# Carte_Affichage.net
KiCad netlist of a schematic drawn in EAGLE
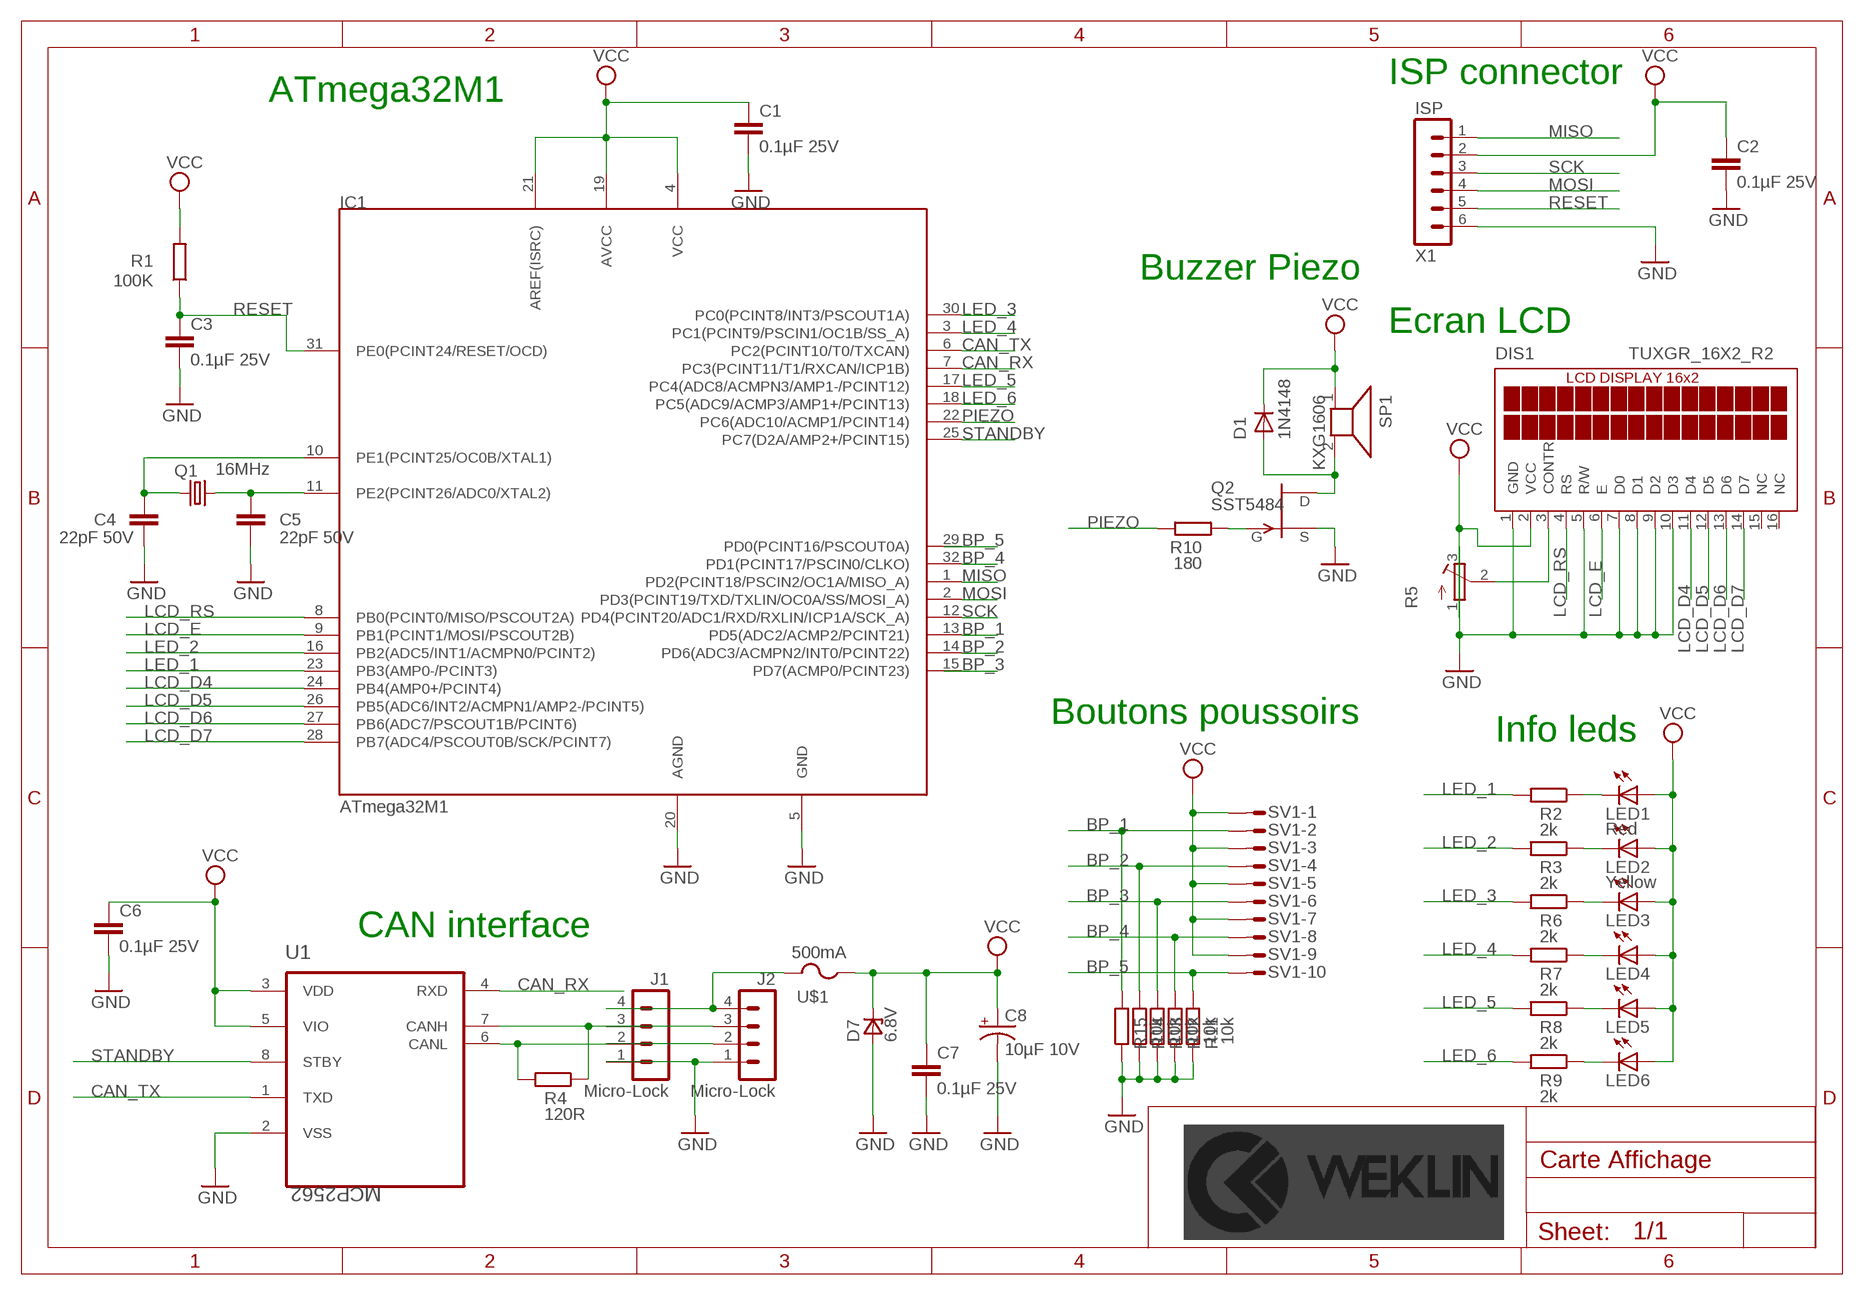
[diagram p0: schematic, sheet 1]

(export (version "E")
  (design (tool "Eeschema 10.0.6"))
  (components
    (comp (ref "C1")
      (value "0.1µF 25V")
      (footprint "eagle-import:C2012")
      (fields (field (name "MANUFACTURER") "AVX") (field (name "MPN") "08053C104KAT2A"))
      (libsource (lib "eagle-import") (part "CAPACITOR_NON_POL-0.1µF-25V(+-10%)(2012)"))
    )
    (comp (ref "C2")
      (value "0.1µF 25V")
      (footprint "eagle-import:C2012")
      (fields (field (name "MANUFACTURER") "AVX") (field (name "MPN") "08053C104KAT2A"))
      (libsource (lib "eagle-import") (part "CAPACITOR_NON_POL-0.1µF-25V(+-10%)(2012)"))
    )
    (comp (ref "C3")
      (value "0.1µF 25V")
      (footprint "eagle-import:C2012")
      (fields (field (name "MANUFACTURER") "AVX") (field (name "MPN") "08053C104KAT2A"))
      (libsource (lib "eagle-import") (part "CAPACITOR_NON_POL-0.1µF-25V(+-10%)(2012)"))
    )
    (comp (ref "C4")
      (value "22pF 50V")
      (footprint "eagle-import:C2012")
      (fields (field (name "MANUFACTURER") "Multicomp") (field (name "MPN") "MC0805N220J500CT"))
      (libsource (lib "eagle-import") (part "CAPACITOR_NON_POL-22PF-50V(+-5%)(2012)"))
    )
    (comp (ref "C5")
      (value "22pF 50V")
      (footprint "eagle-import:C2012")
      (fields (field (name "MANUFACTURER") "Multicomp") (field (name "MPN") "MC0805N220J500CT"))
      (libsource (lib "eagle-import") (part "CAPACITOR_NON_POL-22PF-50V(+-5%)(2012)"))
    )
    (comp (ref "C6")
      (value "0.1µF 25V")
      (footprint "eagle-import:C2012")
      (fields (field (name "MANUFACTURER") "AVX") (field (name "MPN") "08053C104KAT2A"))
      (libsource (lib "eagle-import") (part "CAPACITOR_NON_POL-0.1µF-25V(+-10%)(2012)"))
    )
    (comp (ref "C7")
      (value "0.1µF 25V")
      (footprint "eagle-import:C2012")
      (fields (field (name "MANUFACTURER") "AVX") (field (name "MPN") "08053C104KAT2A"))
      (libsource (lib "eagle-import") (part "CAPACITOR_NON_POL-0.1µF-25V(+-10%)(2012)"))
    )
    (comp (ref "C8")
      (value "10µF 10V")
      (footprint "eagle-import:EIA3216")
      (fields (field (name "MANUFACTURER") "Kemet") (field (name "MPN") "T491A106K010AT"))
      (libsource (lib "eagle-import") (part "CAPACITOR_POL-10µF-10V(+-10%)(3216)"))
    )
    (comp (ref "D1")
      (value "1N4148")
      (footprint "eagle-import:SMA-DO214AC")
      (libsource (lib "eagle-import") (part "GF1"))
    )
    (comp (ref "D7")
      (value "6.8V")
      (footprint "eagle-import:DO-214AA")
      (fields (field (name "MANUFACTURER") "ON Semiconductor") (field (name "MPN") "P6SMB6.8AT3G"))
      (libsource (lib "eagle-import") (part "ZENER_UNIDIR6.8"))
    )
    (comp (ref "DIS1")
      (value "TUXGR_16X2_R2")
      (footprint "eagle-import:TUXGR_16X2_R2")
      (libsource (lib "eagle-import") (part "TUXGR_16X2_R2"))
    )
    (comp (ref "IC1")
      (value "ATmega32M1")
      (footprint "eagle-import:TQFP32")
      (fields (field (name "MANUFACTURER") "Atmel") (field (name "MPN") "ATmega32M1-AU"))
      (libsource (lib "eagle-import") (part "ATMEGA32M1-TQFP32"))
    )
    (comp (ref "J1")
      (value "Micro-Lock")
      (footprint "eagle-import:504195-0470")
      (fields (field (name "MANUFACTURER") "Molex") (field (name "MPN") "504195-0470"))
      (libsource (lib "eagle-import") (part "MICROLOCK-4CMS"))
    )
    (comp (ref "J2")
      (value "Micro-Lock")
      (footprint "eagle-import:504195-0470")
      (fields (field (name "MANUFACTURER") "Molex") (field (name "MPN") "504195-0470"))
      (libsource (lib "eagle-import") (part "MICROLOCK-4CMS"))
    )
    (comp (ref "LED1")
      (value "Red")
      (footprint "eagle-import:VLD")
      (fields (field (name "MANUFACTURER") "Vishay") (field (name "MPN") "VLDS1235G"))
      (libsource (lib "eagle-import") (part "LEDVLDS1235G"))
    )
    (comp (ref "LED2")
      (value "Yellow")
      (footprint "eagle-import:VLD")
      (fields (field (name "MANUFACTURER") "Vishay") (field (name "MPN") "VLDY1235G"))
      (libsource (lib "eagle-import") (part "LED-VLDY1235G"))
    )
    (comp (ref "LED3")
      (value "LED5MM")
      (footprint "eagle-import:LED5MM")
      (libsource (lib "eagle-import") (part "LED5MM"))
    )
    (comp (ref "LED4")
      (value "LED5MM")
      (footprint "eagle-import:LED5MM")
      (libsource (lib "eagle-import") (part "LED5MM"))
    )
    (comp (ref "LED5")
      (value "LED5MM")
      (footprint "eagle-import:LED5MM")
      (libsource (lib "eagle-import") (part "LED5MM"))
    )
    (comp (ref "LED6")
      (value "LED5MM")
      (footprint "eagle-import:LED5MM")
      (libsource (lib "eagle-import") (part "LED5MM"))
    )
    (comp (ref "Q1")
      (value "16MHz")
      (footprint "eagle-import:SMD_KX7")
      (fields (field (name "MANUFACTURER") "AEL CRYSTALS") (field (name "MPN") "E3SB16.0000F09G11AE"))
      (libsource (lib "eagle-import") (part "CRYSTAL-16MHZ_SMD(3225)"))
    )
    (comp (ref "Q2")
      (value "SST5484")
      (footprint "eagle-import:SOT23")
      (libsource (lib "eagle-import") (part "?548SST4"))
    )
    (comp (ref "R1")
      (value "100K")
      (footprint "eagle-import:R2012")
      (fields (field (name "MANUFACTURER") "Multicomp") (field (name "MPN") "MCWR08X1003FTL"))
      (libsource (lib "eagle-import") (part "RESISTOR-100K(+-1%)(2012)"))
    )
    (comp (ref "R2")
      (value "2k")
      (footprint "eagle-import:R2012")
      (fields (field (name "MANUFACTURER") "Multicomp") (field (name "MPN") "MC0805S8F1101T5E"))
      (libsource (lib "eagle-import") (part "RESISTOR-1K1(+-1%)(2012)"))
    )
    (comp (ref "R3")
      (value "2k")
      (footprint "eagle-import:R2012")
      (fields (field (name "MANUFACTURER") "Multicomp") (field (name "MPN") "MC0805S8F1101T5E"))
      (libsource (lib "eagle-import") (part "RESISTOR-1K1(+-1%)(2012)"))
    )
    (comp (ref "R4")
      (value "120R")
      (footprint "eagle-import:R2012")
      (fields (field (name "MANUFACTURER") "Multicomp") (field (name "MPN") "MCWR08X1200FTL"))
      (libsource (lib "eagle-import") (part "RESISTOR-120R(+-1%)(2012)"))
    )
    (comp (ref "R5")
      (value "R-TRIMM3299W")
      (footprint "eagle-import:RTRIM3299W")
      (libsource (lib "eagle-import") (part "R-TRIMM3299W"))
    )
    (comp (ref "R6")
      (value "2k")
      (footprint "eagle-import:R2012")
      (fields (field (name "MANUFACTURER") "Multicomp") (field (name "MPN") "MC0805S8F1101T5E"))
      (libsource (lib "eagle-import") (part "RESISTOR-1K1(+-1%)(2012)"))
    )
    (comp (ref "R7")
      (value "2k")
      (footprint "eagle-import:R2012")
      (fields (field (name "MANUFACTURER") "Multicomp") (field (name "MPN") "MC0805S8F1101T5E"))
      (libsource (lib "eagle-import") (part "RESISTOR-1K1(+-1%)(2012)"))
    )
    (comp (ref "R8")
      (value "2k")
      (footprint "eagle-import:R2012")
      (fields (field (name "MANUFACTURER") "Multicomp") (field (name "MPN") "MC0805S8F1101T5E"))
      (libsource (lib "eagle-import") (part "RESISTOR-1K1(+-1%)(2012)"))
    )
    (comp (ref "R9")
      (value "2k")
      (footprint "eagle-import:R2012")
      (fields (field (name "MANUFACTURER") "Multicomp") (field (name "MPN") "MC0805S8F1101T5E"))
      (libsource (lib "eagle-import") (part "RESISTOR-1K1(+-1%)(2012)"))
    )
    (comp (ref "R10")
      (value "180")
      (footprint "eagle-import:R2012")
      (fields (field (name "MANUFACTURER") "Multicomp") (field (name "MPN") "MC0805S8F1101T5E"))
      (libsource (lib "eagle-import") (part "RESISTOR-1K1(+-1%)(2012)"))
    )
    (comp (ref "R11")
      (value "10k")
      (footprint "eagle-import:R2012")
      (fields (field (name "MANUFACTURER") "Multicomp") (field (name "MPN") "MC0805S8F1101T5E"))
      (libsource (lib "eagle-import") (part "RESISTOR-1K1(+-1%)(2012)"))
    )
    (comp (ref "R12")
      (value "10k")
      (footprint "eagle-import:R2012")
      (fields (field (name "MANUFACTURER") "Multicomp") (field (name "MPN") "MC0805S8F1101T5E"))
      (libsource (lib "eagle-import") (part "RESISTOR-1K1(+-1%)(2012)"))
    )
    (comp (ref "R13")
      (value "10k")
      (footprint "eagle-import:R2012")
      (fields (field (name "MANUFACTURER") "Multicomp") (field (name "MPN") "MC0805S8F1101T5E"))
      (libsource (lib "eagle-import") (part "RESISTOR-1K1(+-1%)(2012)"))
    )
    (comp (ref "R14")
      (value "10k")
      (footprint "eagle-import:R2012")
      (fields (field (name "MANUFACTURER") "Multicomp") (field (name "MPN") "MC0805S8F1101T5E"))
      (libsource (lib "eagle-import") (part "RESISTOR-1K1(+-1%)(2012)"))
    )
    (comp (ref "R15")
      (value "10k")
      (footprint "eagle-import:R2012")
      (fields (field (name "MANUFACTURER") "Multicomp") (field (name "MPN") "MC0805S8F1101T5E"))
      (libsource (lib "eagle-import") (part "RESISTOR-1K1(+-1%)(2012)"))
    )
    (comp (ref "SP1")
      (value "KXG1606")
      (footprint "eagle-import:AL23P")
      (libsource (lib "eagle-import") (part "AL23P"))
    )
    (comp (ref "SV1")
      (value "S10P")
      (footprint "eagle-import:S10P2")
      (libsource (lib "eagle-import") (part "S10P"))
    )
    (comp (ref "U$1")
      (value "500mA")
      (footprint "eagle-import:EIARS-481-2")
      (fields (field (name "MANUFACTURER") "Littlefuse") (field (name "MPN") "0451.500MRL"))
      (libsource (lib "eagle-import") (part "FUSE"))
    )
    (comp (ref "U1")
      (value "MCP2562")
      (footprint "eagle-import:SOIC8")
      (fields (field (name "MANUFACTURER") "Microchip") (field (name "MPN") "MCP2562-E/SN"))
      (libsource (lib "eagle-import") (part "MCP2562-E/SN-SOIC8"))
    )
    (comp (ref "X1")
      (value "ISP")
      (footprint "eagle-import:MINITEK_127_6WAY_SMD")
      (fields (field (name "MANUFACTURER") "Minitek") (field (name "MPN") "20021121-00006C4LF"))
      (libsource (lib "eagle-import") (part "MINITEK_127_6WAYS-SMD"))
    )
  )
  (nets
    (net (code "1") (name "/BP_1") (class "Default")
      (node (ref "IC1") (pin "13") (pinfunction "PD5(ADC2/ACMP2/PCINT21)_13") (pintype "bidirectional"))
      (node (ref "R15") (pin "2") (pinfunction "2_2") (pintype "passive"))
      (node (ref "SV1") (pin "P$2") (pinfunction "S_P$2") (pintype "passive"))
    )
    (net (code "2") (name "/BP_2") (class "Default")
      (node (ref "IC1") (pin "14") (pinfunction "PD6(ADC3/ACMPN2/INT0/PCINT22)_14") (pintype "bidirectional"))
      (node (ref "R14") (pin "2") (pinfunction "2_2") (pintype "passive"))
      (node (ref "SV1") (pin "P$4") (pinfunction "S_P$4") (pintype "passive"))
    )
    (net (code "3") (name "/BP_3") (class "Default")
      (node (ref "IC1") (pin "15") (pinfunction "PD7(ACMP0/PCINT23)_15") (pintype "bidirectional"))
      (node (ref "R13") (pin "2") (pinfunction "2_2") (pintype "passive"))
      (node (ref "SV1") (pin "P$6") (pinfunction "S_P$6") (pintype "passive"))
    )
    (net (code "4") (name "/BP_4") (class "Default")
      (node (ref "IC1") (pin "32") (pinfunction "PD1(PCINT17/PSCIN0/CLKO)_32") (pintype "bidirectional"))
      (node (ref "R12") (pin "2") (pinfunction "2_2") (pintype "passive"))
      (node (ref "SV1") (pin "P$8") (pinfunction "S_P$8") (pintype "passive"))
    )
    (net (code "5") (name "/BP_5") (class "Default")
      (node (ref "IC1") (pin "29") (pinfunction "PD0(PCINT16/PSCOUT0A)_29") (pintype "bidirectional"))
      (node (ref "R11") (pin "2") (pinfunction "2_2") (pintype "passive"))
      (node (ref "SV1") (pin "P$10") (pinfunction "S_P$10") (pintype "passive"))
    )
    (net (code "6") (name "/CAN_RX") (class "Default")
      (node (ref "IC1") (pin "7") (pinfunction "PC3(PCINT11/T1/RXCAN/ICP1B)_7") (pintype "bidirectional"))
      (node (ref "U1") (pin "4") (pinfunction "RXD_4") (pintype "output"))
    )
    (net (code "7") (name "/CAN_TX") (class "Default")
      (node (ref "IC1") (pin "6") (pinfunction "PC2(PCINT10/T0/TXCAN)_6") (pintype "bidirectional"))
      (node (ref "U1") (pin "1") (pinfunction "TXD_1") (pintype "input"))
    )
    (net (code "8") (name "/LCD_D4") (class "Default")
      (node (ref "DIS1") (pin "11") (pinfunction "D4_11") (pintype "input"))
      (node (ref "IC1") (pin "24") (pinfunction "PB4(AMP0+/PCINT4)_24") (pintype "bidirectional"))
    )
    (net (code "9") (name "/LCD_D5") (class "Default")
      (node (ref "DIS1") (pin "12") (pinfunction "D5_12") (pintype "input"))
      (node (ref "IC1") (pin "26") (pinfunction "PB5(ADC6/INT2/ACMPN1/AMP2-/PCINT5)_26") (pintype "bidirectional"))
    )
    (net (code "10") (name "/LCD_D6") (class "Default")
      (node (ref "DIS1") (pin "13") (pinfunction "D6_13") (pintype "input"))
      (node (ref "IC1") (pin "27") (pinfunction "PB6(ADC7/PSCOUT1B/PCINT6)_27") (pintype "bidirectional"))
    )
    (net (code "11") (name "/LCD_D7") (class "Default")
      (node (ref "DIS1") (pin "14") (pinfunction "D7_14") (pintype "input"))
      (node (ref "IC1") (pin "28") (pinfunction "PB7(ADC4/PSCOUT0B/SCK/PCINT7)_28") (pintype "bidirectional"))
    )
    (net (code "12") (name "/LCD_E") (class "Default")
      (node (ref "DIS1") (pin "6") (pinfunction "E_6") (pintype "input"))
      (node (ref "IC1") (pin "9") (pinfunction "PB1(PCINT1/MOSI/PSCOUT2B)_9") (pintype "bidirectional"))
    )
    (net (code "13") (name "/LCD_RS") (class "Default")
      (node (ref "DIS1") (pin "4") (pinfunction "RS_4") (pintype "input"))
      (node (ref "IC1") (pin "8") (pinfunction "PB0(PCINT0/MISO/PSCOUT2A)_8") (pintype "bidirectional"))
    )
    (net (code "14") (name "/LED_1") (class "Default")
      (node (ref "IC1") (pin "23") (pinfunction "PB3(AMP0-/PCINT3)_23") (pintype "bidirectional"))
      (node (ref "R2") (pin "2") (pinfunction "2_2") (pintype "passive"))
    )
    (net (code "15") (name "/LED_2") (class "Default")
      (node (ref "IC1") (pin "16") (pinfunction "PB2(ADC5/INT1/ACMPN0/PCINT2)_16") (pintype "bidirectional"))
      (node (ref "R3") (pin "2") (pinfunction "2_2") (pintype "passive"))
    )
    (net (code "16") (name "/LED_3") (class "Default")
      (node (ref "IC1") (pin "30") (pinfunction "PC0(PCINT8/INT3/PSCOUT1A)_30") (pintype "bidirectional"))
      (node (ref "R6") (pin "2") (pinfunction "2_2") (pintype "passive"))
    )
    (net (code "17") (name "/LED_4") (class "Default")
      (node (ref "IC1") (pin "3") (pinfunction "PC1(PCINT9/PSCIN1/OC1B/SS_A)_3") (pintype "bidirectional"))
      (node (ref "R7") (pin "2") (pinfunction "2_2") (pintype "passive"))
    )
    (net (code "18") (name "/LED_5") (class "Default")
      (node (ref "IC1") (pin "17") (pinfunction "PC4(ADC8/ACMPN3/AMP1-/PCINT12)_17") (pintype "bidirectional"))
      (node (ref "R8") (pin "2") (pinfunction "2_2") (pintype "passive"))
    )
    (net (code "19") (name "/LED_6") (class "Default")
      (node (ref "IC1") (pin "18") (pinfunction "PC5(ADC9/ACMP3/AMP1+/PCINT13)_18") (pintype "bidirectional"))
      (node (ref "R9") (pin "2") (pinfunction "2_2") (pintype "passive"))
    )
    (net (code "20") (name "/MISO") (class "Default")
      (node (ref "IC1") (pin "1") (pinfunction "PD2(PCINT18/PSCIN2/OC1A/MISO_A)_1") (pintype "bidirectional"))
      (node (ref "X1") (pin "1") (pinfunction "1_1") (pintype "passive"))
    )
    (net (code "21") (name "/MOSI") (class "Default")
      (node (ref "IC1") (pin "2") (pinfunction "PD3(PCINT19/TXD/TXLIN/OC0A/SS/MOSI_A)_2") (pintype "bidirectional"))
      (node (ref "X1") (pin "4") (pinfunction "4_4") (pintype "passive"))
    )
    (net (code "22") (name "/PIEZO") (class "Default")
      (node (ref "IC1") (pin "22") (pinfunction "PC6(ADC10/ACMP1/PCINT14)_22") (pintype "bidirectional"))
      (node (ref "R10") (pin "1") (pinfunction "1_1") (pintype "passive"))
    )
    (net (code "23") (name "/RESET") (class "Default")
      (node (ref "C3") (pin "1") (pinfunction "1_1") (pintype "passive"))
      (node (ref "IC1") (pin "31") (pinfunction "PE0(PCINT24/RESET/OCD)_31") (pintype "bidirectional"))
      (node (ref "R1") (pin "1") (pinfunction "1_1") (pintype "passive"))
      (node (ref "X1") (pin "5") (pinfunction "5_5") (pintype "passive"))
    )
    (net (code "24") (name "/SCK") (class "Default")
      (node (ref "IC1") (pin "12") (pinfunction "PD4(PCINT20/ADC1/RXD/RXLIN/ICP1A/SCK_A)_12") (pintype "bidirectional"))
      (node (ref "X1") (pin "3") (pinfunction "3_3") (pintype "passive"))
    )
    (net (code "25") (name "/STANDBY") (class "Default")
      (node (ref "IC1") (pin "25") (pinfunction "PC7(D2A/AMP2+/PCINT15)_25") (pintype "bidirectional"))
      (node (ref "U1") (pin "8") (pinfunction "STBY_8") (pintype "input"))
    )
    (net (code "26") (name "GND") (class "Default")
      (node (ref "C1") (pin "2") (pinfunction "2_2") (pintype "passive"))
      (node (ref "C2") (pin "2") (pinfunction "2_2") (pintype "passive"))
      (node (ref "C3") (pin "2") (pinfunction "2_2") (pintype "passive"))
      (node (ref "C4") (pin "2") (pinfunction "2_2") (pintype "passive"))
      (node (ref "C5") (pin "2") (pinfunction "2_2") (pintype "passive"))
      (node (ref "C6") (pin "2") (pinfunction "2_2") (pintype "passive"))
      (node (ref "C7") (pin "2") (pinfunction "2_2") (pintype "passive"))
      (node (ref "C8") (pin "C") (pinfunction "-_C") (pintype "passive"))
      (node (ref "D7") (pin "A") (pinfunction "A_A") (pintype "passive"))
      (node (ref "DIS1") (pin "1") (pinfunction "GND_1") (pintype "power_in"))
      (node (ref "DIS1") (pin "10") (pinfunction "D3_10") (pintype "input"))
      (node (ref "DIS1") (pin "5") (pinfunction "R/W_5") (pintype "input"))
      (node (ref "DIS1") (pin "7") (pinfunction "D0_7") (pintype "input"))
      (node (ref "DIS1") (pin "8") (pinfunction "D1_8") (pintype "input"))
      (node (ref "DIS1") (pin "9") (pinfunction "D2_9") (pintype "input"))
      (node (ref "IC1") (pin "20") (pinfunction "AGND_20") (pintype "power_in"))
      (node (ref "IC1") (pin "5") (pinfunction "GND_5") (pintype "power_in"))
      (node (ref "J1") (pin "1") (pinfunction "1_1") (pintype "passive"))
      (node (ref "J2") (pin "1") (pinfunction "1_1") (pintype "passive"))
      (node (ref "Q2") (pin "2") (pinfunction "S_2") (pintype "passive"))
      (node (ref "R11") (pin "1") (pinfunction "1_1") (pintype "passive"))
      (node (ref "R12") (pin "1") (pinfunction "1_1") (pintype "passive"))
      (node (ref "R13") (pin "1") (pinfunction "1_1") (pintype "passive"))
      (node (ref "R14") (pin "1") (pinfunction "1_1") (pintype "passive"))
      (node (ref "R15") (pin "1") (pinfunction "1_1") (pintype "passive"))
      (node (ref "R5") (pin "3") (pinfunction "A_3") (pintype "passive"))
      (node (ref "U1") (pin "2") (pinfunction "VSS_2") (pintype "power_in"))
      (node (ref "X1") (pin "6") (pinfunction "6_6") (pintype "passive"))
    )
    (net (code "27") (name "Net-(DIS1-CONTR)") (class "Default")
      (node (ref "DIS1") (pin "3") (pinfunction "CONTR_3") (pintype "input"))
      (node (ref "R5") (pin "2") (pinfunction "S_2") (pintype "passive"))
    )
    (net (code "28") (name "Net-(IC1-PE1(PCINT25{slash}OC0B{slash}XTAL1))") (class "Default")
      (node (ref "C4") (pin "1") (pinfunction "1_1") (pintype "passive"))
      (node (ref "IC1") (pin "10") (pinfunction "PE1(PCINT25/OC0B/XTAL1)_10") (pintype "bidirectional"))
      (node (ref "Q1") (pin "1") (pinfunction "1_1") (pintype "passive"))
    )
    (net (code "29") (name "Net-(IC1-PE2(PCINT26{slash}ADC0{slash}XTAL2))") (class "Default")
      (node (ref "C5") (pin "1") (pinfunction "1_1") (pintype "passive"))
      (node (ref "IC1") (pin "11") (pinfunction "PE2(PCINT26/ADC0/XTAL2)_11") (pintype "bidirectional"))
      (node (ref "Q1") (pin "3") (pinfunction "2_3") (pintype "passive"))
    )
    (net (code "30") (name "Net-(J1-Pad4)") (class "Default")
      (node (ref "J1") (pin "4") (pinfunction "4_4") (pintype "passive"))
      (node (ref "J2") (pin "4") (pinfunction "4_4") (pintype "passive"))
      (node (ref "U$1") (pin "2") (pinfunction "2_2") (pintype "passive"))
    )
    (net (code "31") (name "Net-(LED1-PadC)") (class "Default")
      (node (ref "LED1") (pin "C") (pinfunction "C_C") (pintype "passive"))
      (node (ref "R2") (pin "1") (pinfunction "1_1") (pintype "passive"))
    )
    (net (code "32") (name "Net-(LED2-PadC)") (class "Default")
      (node (ref "LED2") (pin "C") (pinfunction "C_C") (pintype "passive"))
      (node (ref "R3") (pin "1") (pinfunction "1_1") (pintype "passive"))
    )
    (net (code "33") (name "Net-(LED3-C)") (class "Default")
      (node (ref "LED3") (pin "K") (pinfunction "C_K") (pintype "passive"))
      (node (ref "R6") (pin "1") (pinfunction "1_1") (pintype "passive"))
    )
    (net (code "34") (name "Net-(LED4-C)") (class "Default")
      (node (ref "LED4") (pin "K") (pinfunction "C_K") (pintype "passive"))
      (node (ref "R7") (pin "1") (pinfunction "1_1") (pintype "passive"))
    )
    (net (code "35") (name "Net-(LED5-C)") (class "Default")
      (node (ref "LED5") (pin "K") (pinfunction "C_K") (pintype "passive"))
      (node (ref "R8") (pin "1") (pinfunction "1_1") (pintype "passive"))
    )
    (net (code "36") (name "Net-(LED6-C)") (class "Default")
      (node (ref "LED6") (pin "K") (pinfunction "C_K") (pintype "passive"))
      (node (ref "R9") (pin "1") (pinfunction "1_1") (pintype "passive"))
    )
    (net (code "37") (name "Net-(Q2-D)") (class "Default")
      (node (ref "D1") (pin "A") (pinfunction "A_A") (pintype "passive"))
      (node (ref "Q2") (pin "1") (pinfunction "D_1") (pintype "passive"))
      (node (ref "SP1") (pin "2") (pinfunction "2_2") (pintype "passive"))
    )
    (net (code "38") (name "Net-(Q2-G)") (class "Default")
      (node (ref "Q2") (pin "3") (pinfunction "G_3") (pintype "passive"))
      (node (ref "R10") (pin "2") (pinfunction "2_2") (pintype "passive"))
    )
    (net (code "39") (name "Net-(U1-CANH)") (class "Default")
      (node (ref "J1") (pin "3") (pinfunction "3_3") (pintype "passive"))
      (node (ref "J2") (pin "3") (pinfunction "3_3") (pintype "passive"))
      (node (ref "R4") (pin "1") (pinfunction "1_1") (pintype "passive"))
      (node (ref "U1") (pin "7") (pinfunction "CANH_7") (pintype "bidirectional"))
    )
    (net (code "40") (name "Net-(U1-CANL)") (class "Default")
      (node (ref "J1") (pin "2") (pinfunction "2_2") (pintype "passive"))
      (node (ref "J2") (pin "2") (pinfunction "2_2") (pintype "passive"))
      (node (ref "R4") (pin "2") (pinfunction "2_2") (pintype "passive"))
      (node (ref "U1") (pin "6") (pinfunction "CANL_6") (pintype "bidirectional"))
    )
    (net (code "41") (name "VCC") (class "Default")
      (node (ref "C1") (pin "1") (pinfunction "1_1") (pintype "passive"))
      (node (ref "C2") (pin "1") (pinfunction "1_1") (pintype "passive"))
      (node (ref "C6") (pin "1") (pinfunction "1_1") (pintype "passive"))
      (node (ref "C7") (pin "1") (pinfunction "1_1") (pintype "passive"))
      (node (ref "C8") (pin "A") (pinfunction "+_A") (pintype "passive"))
      (node (ref "D1") (pin "K") (pinfunction "C_K") (pintype "passive"))
      (node (ref "D7") (pin "C") (pinfunction "C_C") (pintype "passive"))
      (node (ref "DIS1") (pin "2") (pinfunction "VCC_2") (pintype "power_in"))
      (node (ref "IC1") (pin "19") (pinfunction "AVCC_19") (pintype "power_in"))
      (node (ref "IC1") (pin "21") (pinfunction "AREF(ISRC)_21") (pintype "power_in"))
      (node (ref "IC1") (pin "4") (pinfunction "VCC_4") (pintype "power_in"))
      (node (ref "LED1") (pin "A") (pinfunction "A_A") (pintype "passive"))
      (node (ref "LED2") (pin "A") (pinfunction "A_A") (pintype "passive"))
      (node (ref "LED3") (pin "A") (pinfunction "A_A") (pintype "passive"))
      (node (ref "LED4") (pin "A") (pinfunction "A_A") (pintype "passive"))
      (node (ref "LED5") (pin "A") (pinfunction "A_A") (pintype "passive"))
      (node (ref "LED6") (pin "A") (pinfunction "A_A") (pintype "passive"))
      (node (ref "R1") (pin "2") (pinfunction "2_2") (pintype "passive"))
      (node (ref "R5") (pin "1") (pinfunction "E_1") (pintype "passive"))
      (node (ref "SP1") (pin "1") (pinfunction "1_1") (pintype "passive"))
      (node (ref "SV1") (pin "P$1") (pinfunction "S_P$1") (pintype "passive"))
      (node (ref "SV1") (pin "P$3") (pinfunction "S_P$3") (pintype "passive"))
      (node (ref "SV1") (pin "P$5") (pinfunction "S_P$5") (pintype "passive"))
      (node (ref "SV1") (pin "P$7") (pinfunction "S_P$7") (pintype "passive"))
      (node (ref "SV1") (pin "P$9") (pinfunction "S_P$9") (pintype "passive"))
      (node (ref "U$1") (pin "1") (pinfunction "1_1") (pintype "passive"))
      (node (ref "U1") (pin "3") (pinfunction "VDD_3") (pintype "power_in"))
      (node (ref "U1") (pin "5") (pinfunction "VIO_5") (pintype "power_in"))
      (node (ref "X1") (pin "2") (pinfunction "2_2") (pintype "passive"))
    )
    (net (code "42") (name "unconnected-(DIS1-NC-Pad15)") (class "Default")
      (node (ref "DIS1") (pin "15") (pinfunction "NC_15") (pintype "no_connect"))
    )
    (net (code "43") (name "unconnected-(DIS1-NC-Pad16)") (class "Default")
      (node (ref "DIS1") (pin "16") (pinfunction "NC_16") (pintype "no_connect"))
    )
  )
)
